# Sheet2.net
KiCad netlist of a schematic drawn in Altium Designer
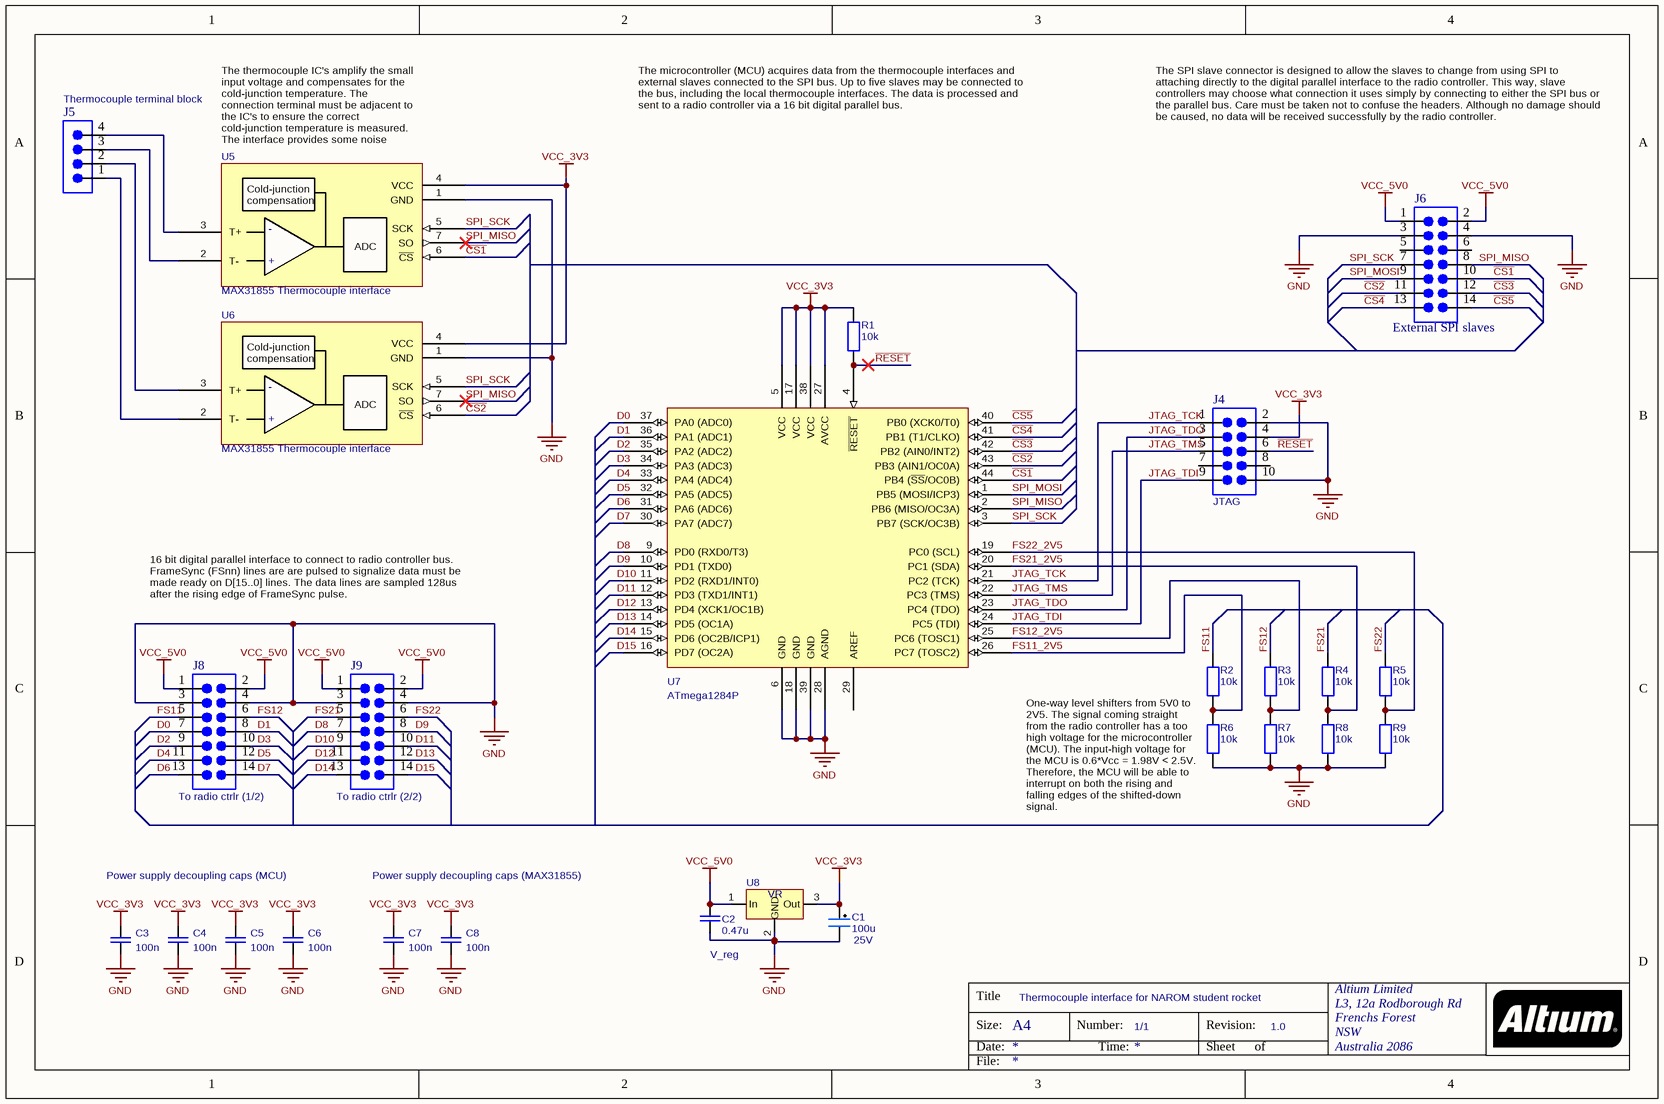
[diagram p0: Sheet2.SchDoc]

(export (version "E")
  (design (tool "Eeschema 10.0.6"))
  (components
    (comp (ref "C1")
      (value "100u")
      (footprint "cap_alu_electrolyte_size_code_e")
      (description "Generic polar capacitor")
      (fields (field (name "VOLTAGE RATING") "25V"))
      (libsource (lib "Schlib1") (part "cap_genCap_polar"))
    )
    (comp (ref "C2")
      (value "0.47u")
      (footprint "cap_0603_standard")
      (description "Generic unipolarised capasitor")
      (libsource (lib "LabLib") (part "cap__genCapUnipol"))
    )
    (comp (ref "C3")
      (value "100n")
      (footprint "cap_0603_standard")
      (description "Generic unipolarised capasitor")
      (libsource (lib "LabLib") (part "cap__genCapUnipol"))
    )
    (comp (ref "C4")
      (value "100n")
      (footprint "cap_0603_standard")
      (description "Generic unipolarised capasitor")
      (libsource (lib "LabLib") (part "cap__genCapUnipol"))
    )
    (comp (ref "C5")
      (value "100n")
      (footprint "cap_0603_standard")
      (description "Generic unipolarised capasitor")
      (libsource (lib "LabLib") (part "cap__genCapUnipol"))
    )
    (comp (ref "C6")
      (value "100n")
      (footprint "cap_0603_standard")
      (description "Generic unipolarised capasitor")
      (libsource (lib "LabLib") (part "cap__genCapUnipol"))
    )
    (comp (ref "C7")
      (value "100n")
      (footprint "cap_0603_standard")
      (description "Generic unipolarised capasitor")
      (libsource (lib "LabLib") (part "cap__genCapUnipol"))
    )
    (comp (ref "C8")
      (value "100n")
      (footprint "cap_0603_standard")
      (description "Generic unipolarised capasitor")
      (libsource (lib "LabLib") (part "cap__genCapUnipol"))
    )
    (comp (ref "J4")
      (value "JTAG")
      (footprint "SHF-105-01-X-D-SM")
      (description "Header 2x5pin")
      (libsource (lib "LabLib") (part "con_head_2x05pin"))
    )
    (comp (ref "J5")
      (value "Thermocouple terminal block")
      (footprint "con_harting_spring_cage_4way")
      (description "Header 1x4pin")
      (libsource (lib "LabLib") (part "con_head_1x04pin"))
    )
    (comp (ref "J6")
      (value "External SPI slaves")
      (footprint "con_datamate_2row_14pin")
      (description "Header 2x7pin")
      (libsource (lib "LabLib") (part "con_head_2x07pin"))
    )
    (comp (ref "J8")
      (value "To radio ctrlr (1/2)")
      (footprint "con_datamate_2row_14pin")
      (description "Header 2x7pin")
      (libsource (lib "LabLib") (part "con_head_2x07pin"))
    )
    (comp (ref "J9")
      (value "To radio ctrlr (2/2)")
      (footprint "con_datamate_2row_14pin")
      (description "Header 2x7pin")
      (libsource (lib "LabLib") (part "con_head_2x07pin"))
    )
    (comp (ref "R1")
      (value "10k")
      (footprint "res_0603_standard")
      (description "Generic resistor")
      (libsource (lib "LabLib") (part "res__genResistor"))
    )
    (comp (ref "R2")
      (value "10k")
      (footprint "res_0603_standard")
      (description "Generic resistor")
      (libsource (lib "LabLib") (part "res__genResistor"))
    )
    (comp (ref "R3")
      (value "10k")
      (footprint "res_0603_standard")
      (description "Generic resistor")
      (libsource (lib "LabLib") (part "res__genResistor"))
    )
    (comp (ref "R4")
      (value "10k")
      (footprint "res_0603_standard")
      (description "Generic resistor")
      (libsource (lib "LabLib") (part "res__genResistor"))
    )
    (comp (ref "R5")
      (value "10k")
      (footprint "res_0603_standard")
      (description "Generic resistor")
      (libsource (lib "LabLib") (part "res__genResistor"))
    )
    (comp (ref "R6")
      (value "10k")
      (footprint "res_0603_standard")
      (description "Generic resistor")
      (libsource (lib "LabLib") (part "res__genResistor"))
    )
    (comp (ref "R7")
      (value "10k")
      (footprint "res_0603_standard")
      (description "Generic resistor")
      (libsource (lib "LabLib") (part "res__genResistor"))
    )
    (comp (ref "R8")
      (value "10k")
      (footprint "res_0603_standard")
      (description "Generic resistor")
      (libsource (lib "LabLib") (part "res__genResistor"))
    )
    (comp (ref "R9")
      (value "10k")
      (footprint "res_0603_standard")
      (description "Generic resistor")
      (libsource (lib "LabLib") (part "res__genResistor"))
    )
    (comp (ref "U5")
      (value "MAX31855 Thermocouple interface")
      (footprint "SO8_N")
      (description "Maxim MAX31855 thermocouple interface")
      (libsource (lib "Schlib1") (part "ic_maxim_max31855_thermocouple_interface_simplified"))
    )
    (comp (ref "U6")
      (value "MAX31855 Thermocouple interface")
      (footprint "SO8_N")
      (description "Maxim MAX31855 thermocouple interface")
      (libsource (lib "Schlib1") (part "ic_maxim_max31855_thermocouple_interface_simplified"))
    )
    (comp (ref "U7")
      (value "ATmega1284P")
      (footprint "ATmega1284P-AU")
      (description "Atmel AVR 8 bit microcontroller")
      (libsource (lib "Schlib1") (part "ic_atmel_atmega1284p_tqfp"))
    )
    (comp (ref "U8")
      (value "V_reg")
      (footprint "ic_lin_reg_lm3940_sot223")
      (description "Positive voltage regulator 78xx")
      (libsource (lib "LabLib") (part "ic_lin_vreg_LM78xx"))
    )
  )
  (nets
    (net (code "1") (name "/D0") (class "Default")
      (node (ref "J8") (pin "7") (pinfunction "7_7") (pintype "passive"))
      (node (ref "U7") (pin "37") (pinfunction "PA0_(ADC0)_37") (pintype "bidirectional"))
    )
    (net (code "2") (name "/D1") (class "Default")
      (node (ref "J8") (pin "8") (pinfunction "8_8") (pintype "passive"))
      (node (ref "U7") (pin "36") (pinfunction "PA1_(ADC1)_36") (pintype "bidirectional"))
    )
    (net (code "3") (name "/D2") (class "Default")
      (node (ref "J8") (pin "9") (pinfunction "9_9") (pintype "passive"))
      (node (ref "U7") (pin "35") (pinfunction "PA2_(ADC2)_35") (pintype "bidirectional"))
    )
    (net (code "4") (name "/D3") (class "Default")
      (node (ref "J8") (pin "10") (pinfunction "10_10") (pintype "passive"))
      (node (ref "U7") (pin "34") (pinfunction "PA3_(ADC3)_34") (pintype "bidirectional"))
    )
    (net (code "5") (name "/D4") (class "Default")
      (node (ref "J8") (pin "11") (pinfunction "11_11") (pintype "passive"))
      (node (ref "U7") (pin "33") (pinfunction "PA4_(ADC4)_33") (pintype "bidirectional"))
    )
    (net (code "6") (name "/D5") (class "Default")
      (node (ref "J8") (pin "12") (pinfunction "12_12") (pintype "passive"))
      (node (ref "U7") (pin "32") (pinfunction "PA5_(ADC5)_32") (pintype "bidirectional"))
    )
    (net (code "7") (name "/D6") (class "Default")
      (node (ref "J8") (pin "13") (pinfunction "13_13") (pintype "passive"))
      (node (ref "U7") (pin "31") (pinfunction "PA6_(ADC6)_31") (pintype "bidirectional"))
    )
    (net (code "8") (name "/D7") (class "Default")
      (node (ref "J8") (pin "14") (pinfunction "14_14") (pintype "passive"))
      (node (ref "U7") (pin "30") (pinfunction "PA7_(ADC7)_30") (pintype "bidirectional"))
    )
    (net (code "9") (name "/D8") (class "Default")
      (node (ref "J9") (pin "7") (pinfunction "7_7") (pintype "passive"))
      (node (ref "U7") (pin "9") (pinfunction "PD0_(RXD0/T3)_9") (pintype "bidirectional"))
    )
    (net (code "10") (name "/D9") (class "Default")
      (node (ref "J9") (pin "8") (pinfunction "8_8") (pintype "passive"))
      (node (ref "U7") (pin "10") (pinfunction "PD1_(TXD0)_10") (pintype "bidirectional"))
    )
    (net (code "11") (name "/D10") (class "Default")
      (node (ref "J9") (pin "9") (pinfunction "9_9") (pintype "passive"))
      (node (ref "U7") (pin "11") (pinfunction "PD2_(RXD1/INT0)_11") (pintype "bidirectional"))
    )
    (net (code "12") (name "/D11") (class "Default")
      (node (ref "J9") (pin "10") (pinfunction "10_10") (pintype "passive"))
      (node (ref "U7") (pin "12") (pinfunction "PD3_(TXD1/INT1)_12") (pintype "bidirectional"))
    )
    (net (code "13") (name "/D12") (class "Default")
      (node (ref "J9") (pin "11") (pinfunction "11_11") (pintype "passive"))
      (node (ref "U7") (pin "13") (pinfunction "PD4_(XCK1/OC1B)_13") (pintype "bidirectional"))
    )
    (net (code "14") (name "/D13") (class "Default")
      (node (ref "J9") (pin "12") (pinfunction "12_12") (pintype "passive"))
      (node (ref "U7") (pin "14") (pinfunction "PD5_(OC1A)_14") (pintype "bidirectional"))
    )
    (net (code "15") (name "/D14") (class "Default")
      (node (ref "J9") (pin "13") (pinfunction "13_13") (pintype "passive"))
      (node (ref "U7") (pin "15") (pinfunction "PD6_(OC2B/ICP1)_15") (pintype "bidirectional"))
    )
    (net (code "16") (name "/D15") (class "Default")
      (node (ref "J9") (pin "14") (pinfunction "14_14") (pintype "passive"))
      (node (ref "U7") (pin "16") (pinfunction "PD7_(OC2A)_16") (pintype "bidirectional"))
    )
    (net (code "17") (name "/FS11") (class "Default")
      (node (ref "J8") (pin "5") (pinfunction "5_5") (pintype "passive"))
      (node (ref "R2") (pin "1") (pinfunction "1_1") (pintype "passive"))
    )
    (net (code "18") (name "/FS11_2V5") (class "Default")
      (node (ref "R2") (pin "2") (pinfunction "2_2") (pintype "passive"))
      (node (ref "R6") (pin "1") (pinfunction "1_1") (pintype "passive"))
      (node (ref "U7") (pin "26") (pinfunction "PC7_(TOSC2)_26") (pintype "bidirectional"))
    )
    (net (code "19") (name "/FS12") (class "Default")
      (node (ref "J8") (pin "6") (pinfunction "6_6") (pintype "passive"))
      (node (ref "R3") (pin "1") (pinfunction "1_1") (pintype "passive"))
    )
    (net (code "20") (name "/FS12_2V5") (class "Default")
      (node (ref "R3") (pin "2") (pinfunction "2_2") (pintype "passive"))
      (node (ref "R7") (pin "1") (pinfunction "1_1") (pintype "passive"))
      (node (ref "U7") (pin "25") (pinfunction "PC6_(TOSC1)_25") (pintype "bidirectional"))
    )
    (net (code "21") (name "/FS21") (class "Default")
      (node (ref "J9") (pin "5") (pinfunction "5_5") (pintype "passive"))
      (node (ref "R4") (pin "1") (pinfunction "1_1") (pintype "passive"))
    )
    (net (code "22") (name "/FS21_2V5") (class "Default")
      (node (ref "R4") (pin "2") (pinfunction "2_2") (pintype "passive"))
      (node (ref "R8") (pin "1") (pinfunction "1_1") (pintype "passive"))
      (node (ref "U7") (pin "20") (pinfunction "PC1_(SDA)_20") (pintype "bidirectional"))
    )
    (net (code "23") (name "/FS22") (class "Default")
      (node (ref "J9") (pin "6") (pinfunction "6_6") (pintype "passive"))
      (node (ref "R5") (pin "1") (pinfunction "1_1") (pintype "passive"))
    )
    (net (code "24") (name "/FS22_2V5") (class "Default")
      (node (ref "R5") (pin "2") (pinfunction "2_2") (pintype "passive"))
      (node (ref "R9") (pin "1") (pinfunction "1_1") (pintype "passive"))
      (node (ref "U7") (pin "19") (pinfunction "PC0_(SCL)_19") (pintype "bidirectional"))
    )
    (net (code "25") (name "/JTAG_TCK") (class "Default")
      (node (ref "J4") (pin "1") (pinfunction "1_1") (pintype "passive"))
      (node (ref "U7") (pin "21") (pinfunction "PC2_(TCK)_21") (pintype "bidirectional"))
    )
    (net (code "26") (name "/JTAG_TDI") (class "Default")
      (node (ref "J4") (pin "9") (pinfunction "9_9") (pintype "passive"))
      (node (ref "U7") (pin "24") (pinfunction "PC5_(TDI)_24") (pintype "bidirectional"))
    )
    (net (code "27") (name "/JTAG_TDO") (class "Default")
      (node (ref "J4") (pin "3") (pinfunction "3_3") (pintype "passive"))
      (node (ref "U7") (pin "23") (pinfunction "PC4_(TDO)_23") (pintype "bidirectional"))
    )
    (net (code "28") (name "/JTAG_TMS") (class "Default")
      (node (ref "J4") (pin "5") (pinfunction "5_5") (pintype "passive"))
      (node (ref "U7") (pin "22") (pinfunction "PC3_(TMS)_22") (pintype "bidirectional"))
    )
    (net (code "29") (name "/SPI_MISO") (class "Default")
      (node (ref "J6") (pin "8") (pinfunction "8_8") (pintype "passive"))
      (node (ref "U5") (pin "7") (pinfunction "SO_7") (pintype "output"))
      (node (ref "U6") (pin "7") (pinfunction "SO_7") (pintype "output"))
      (node (ref "U7") (pin "2") (pinfunction "PB6_(MISO/OC3A)_2") (pintype "bidirectional"))
    )
    (net (code "30") (name "/SPI_MOSI") (class "Default")
      (node (ref "J6") (pin "9") (pinfunction "9_9") (pintype "passive"))
      (node (ref "U7") (pin "1") (pinfunction "PB5_(MOSI/ICP3)_1") (pintype "bidirectional"))
    )
    (net (code "31") (name "/SPI_SCK") (class "Default")
      (node (ref "J6") (pin "7") (pinfunction "7_7") (pintype "passive"))
      (node (ref "U5") (pin "5") (pinfunction "SCK_5") (pintype "input"))
      (node (ref "U6") (pin "5") (pinfunction "SCK_5") (pintype "input"))
      (node (ref "U7") (pin "3") (pinfunction "PB7_(SCK/OC3B)_3") (pintype "bidirectional"))
    )
    (net (code "32") (name "/~{CS1}") (class "Default")
      (node (ref "J6") (pin "10") (pinfunction "10_10") (pintype "passive"))
      (node (ref "U5") (pin "6") (pinfunction "~{CS}_6") (pintype "input"))
      (node (ref "U7") (pin "44") (pinfunction "PB4_(~{SS}/OC0B)_44") (pintype "bidirectional"))
    )
    (net (code "33") (name "/~{CS2}") (class "Default")
      (node (ref "J6") (pin "11") (pinfunction "11_11") (pintype "passive"))
      (node (ref "U6") (pin "6") (pinfunction "~{CS}_6") (pintype "input"))
      (node (ref "U7") (pin "43") (pinfunction "PB3_(AIN1/OC0A)_43") (pintype "bidirectional"))
    )
    (net (code "34") (name "/~{CS3}") (class "Default")
      (node (ref "J6") (pin "12") (pinfunction "12_12") (pintype "passive"))
      (node (ref "U7") (pin "42") (pinfunction "PB2_(AIN0/INT2)_42") (pintype "bidirectional"))
    )
    (net (code "35") (name "/~{CS4}") (class "Default")
      (node (ref "J6") (pin "13") (pinfunction "13_13") (pintype "passive"))
      (node (ref "U7") (pin "41") (pinfunction "PB1_(T1/CLKO)_41") (pintype "bidirectional"))
    )
    (net (code "36") (name "/~{CS5}") (class "Default")
      (node (ref "J6") (pin "14") (pinfunction "14_14") (pintype "passive"))
      (node (ref "U7") (pin "40") (pinfunction "PB0_(XCK0/T0)_40") (pintype "bidirectional"))
    )
    (net (code "37") (name "/~{RESET}") (class "Default")
      (node (ref "J4") (pin "6") (pinfunction "6_6") (pintype "passive"))
      (node (ref "R1") (pin "2") (pinfunction "2_2") (pintype "passive"))
      (node (ref "U7") (pin "4") (pinfunction "~{RESET}_4") (pintype "input"))
    )
    (net (code "38") (name "GND") (class "Default")
      (node (ref "C1") (pin "2") (pintype "passive"))
      (node (ref "C2") (pin "1") (pinfunction "1_1") (pintype "passive"))
      (node (ref "C3") (pin "1") (pinfunction "1_1") (pintype "passive"))
      (node (ref "C4") (pin "1") (pinfunction "1_1") (pintype "passive"))
      (node (ref "C5") (pin "1") (pinfunction "1_1") (pintype "passive"))
      (node (ref "C6") (pin "1") (pinfunction "1_1") (pintype "passive"))
      (node (ref "C7") (pin "1") (pinfunction "1_1") (pintype "passive"))
      (node (ref "C8") (pin "1") (pinfunction "1_1") (pintype "passive"))
      (node (ref "J4") (pin "10") (pinfunction "10_10") (pintype "passive"))
      (node (ref "J4") (pin "2") (pinfunction "2_2") (pintype "passive"))
      (node (ref "J6") (pin "3") (pinfunction "3_3") (pintype "passive"))
      (node (ref "J6") (pin "4") (pinfunction "4_4") (pintype "passive"))
      (node (ref "J8") (pin "3") (pinfunction "3_3") (pintype "passive"))
      (node (ref "J8") (pin "4") (pinfunction "4_4") (pintype "passive"))
      (node (ref "J9") (pin "3") (pinfunction "3_3") (pintype "passive"))
      (node (ref "J9") (pin "4") (pinfunction "4_4") (pintype "passive"))
      (node (ref "R6") (pin "2") (pinfunction "2_2") (pintype "passive"))
      (node (ref "R7") (pin "2") (pinfunction "2_2") (pintype "passive"))
      (node (ref "R8") (pin "2") (pinfunction "2_2") (pintype "passive"))
      (node (ref "R9") (pin "2") (pinfunction "2_2") (pintype "passive"))
      (node (ref "U5") (pin "1") (pinfunction "GND_1") (pintype "power_in"))
      (node (ref "U6") (pin "1") (pinfunction "GND_1") (pintype "power_in"))
      (node (ref "U7") (pin "18") (pinfunction "GND_18") (pintype "power_in"))
      (node (ref "U7") (pin "28") (pinfunction "AGND_28") (pintype "power_in"))
      (node (ref "U7") (pin "39") (pinfunction "GND_39") (pintype "power_in"))
      (node (ref "U7") (pin "6") (pinfunction "GND_6") (pintype "power_in"))
      (node (ref "U8") (pin "2") (pinfunction "GND_2") (pintype "passive"))
    )
    (net (code "39") (name "Net-(U5-T+)") (class "Default")
      (node (ref "J5") (pin "4") (pinfunction "4_4") (pintype "passive"))
      (node (ref "U5") (pin "3") (pinfunction "T+_3") (pintype "passive"))
    )
    (net (code "40") (name "Net-(U5-T-)") (class "Default")
      (node (ref "J5") (pin "3") (pinfunction "3_3") (pintype "passive"))
      (node (ref "U5") (pin "2") (pinfunction "T-_2") (pintype "passive"))
    )
    (net (code "41") (name "Net-(U6-T+)") (class "Default")
      (node (ref "J5") (pin "2") (pinfunction "2_2") (pintype "passive"))
      (node (ref "U6") (pin "3") (pinfunction "T+_3") (pintype "passive"))
    )
    (net (code "42") (name "Net-(U6-T-)") (class "Default")
      (node (ref "J5") (pin "1") (pinfunction "1_1") (pintype "passive"))
      (node (ref "U6") (pin "2") (pinfunction "T-_2") (pintype "passive"))
    )
    (net (code "43") (name "VCC_3V3") (class "Default")
      (node (ref "C1") (pin "1") (pintype "passive"))
      (node (ref "C3") (pin "2") (pinfunction "2_2") (pintype "passive"))
      (node (ref "C4") (pin "2") (pinfunction "2_2") (pintype "passive"))
      (node (ref "C5") (pin "2") (pinfunction "2_2") (pintype "passive"))
      (node (ref "C6") (pin "2") (pinfunction "2_2") (pintype "passive"))
      (node (ref "C7") (pin "2") (pinfunction "2_2") (pintype "passive"))
      (node (ref "C8") (pin "2") (pinfunction "2_2") (pintype "passive"))
      (node (ref "J4") (pin "4") (pinfunction "4_4") (pintype "passive"))
      (node (ref "R1") (pin "1") (pinfunction "1_1") (pintype "passive"))
      (node (ref "U5") (pin "4") (pinfunction "VCC_4") (pintype "power_in"))
      (node (ref "U6") (pin "4") (pinfunction "VCC_4") (pintype "power_in"))
      (node (ref "U7") (pin "17") (pinfunction "VCC_17") (pintype "power_in"))
      (node (ref "U7") (pin "27") (pinfunction "AVCC_27") (pintype "power_in"))
      (node (ref "U7") (pin "38") (pinfunction "VCC_38") (pintype "power_in"))
      (node (ref "U7") (pin "5") (pinfunction "VCC_5") (pintype "power_in"))
      (node (ref "U8") (pin "3") (pinfunction "Out_3") (pintype "passive"))
    )
    (net (code "44") (name "VCC_5V0") (class "Default")
      (node (ref "C2") (pin "2") (pinfunction "2_2") (pintype "passive"))
      (node (ref "J6") (pin "1") (pinfunction "1_1") (pintype "passive"))
      (node (ref "J6") (pin "2") (pinfunction "2_2") (pintype "passive"))
      (node (ref "J8") (pin "1") (pinfunction "1_1") (pintype "passive"))
      (node (ref "J8") (pin "2") (pinfunction "2_2") (pintype "passive"))
      (node (ref "J9") (pin "1") (pinfunction "1_1") (pintype "passive"))
      (node (ref "J9") (pin "2") (pinfunction "2_2") (pintype "passive"))
      (node (ref "U8") (pin "1") (pinfunction "In_1") (pintype "passive"))
    )
    (net (code "45") (name "unconnected-(J4-Pad7)") (class "Default")
      (node (ref "J4") (pin "7") (pinfunction "7_7") (pintype "passive"))
    )
    (net (code "46") (name "unconnected-(J4-Pad8)") (class "Default")
      (node (ref "J4") (pin "8") (pinfunction "8_8") (pintype "passive"))
    )
    (net (code "47") (name "unconnected-(J6-Pad5)") (class "Default")
      (node (ref "J6") (pin "5") (pinfunction "5_5") (pintype "passive"))
    )
    (net (code "48") (name "unconnected-(J6-Pad6)") (class "Default")
      (node (ref "J6") (pin "6") (pinfunction "6_6") (pintype "passive"))
    )
    (net (code "49") (name "unconnected-(U7-AREF-Pad29)") (class "Default")
      (node (ref "U7") (pin "29") (pinfunction "AREF_29") (pintype "passive"))
    )
  )
)
